# MainBoardR4.net
KiCad netlist of a schematic drawn in EAGLE
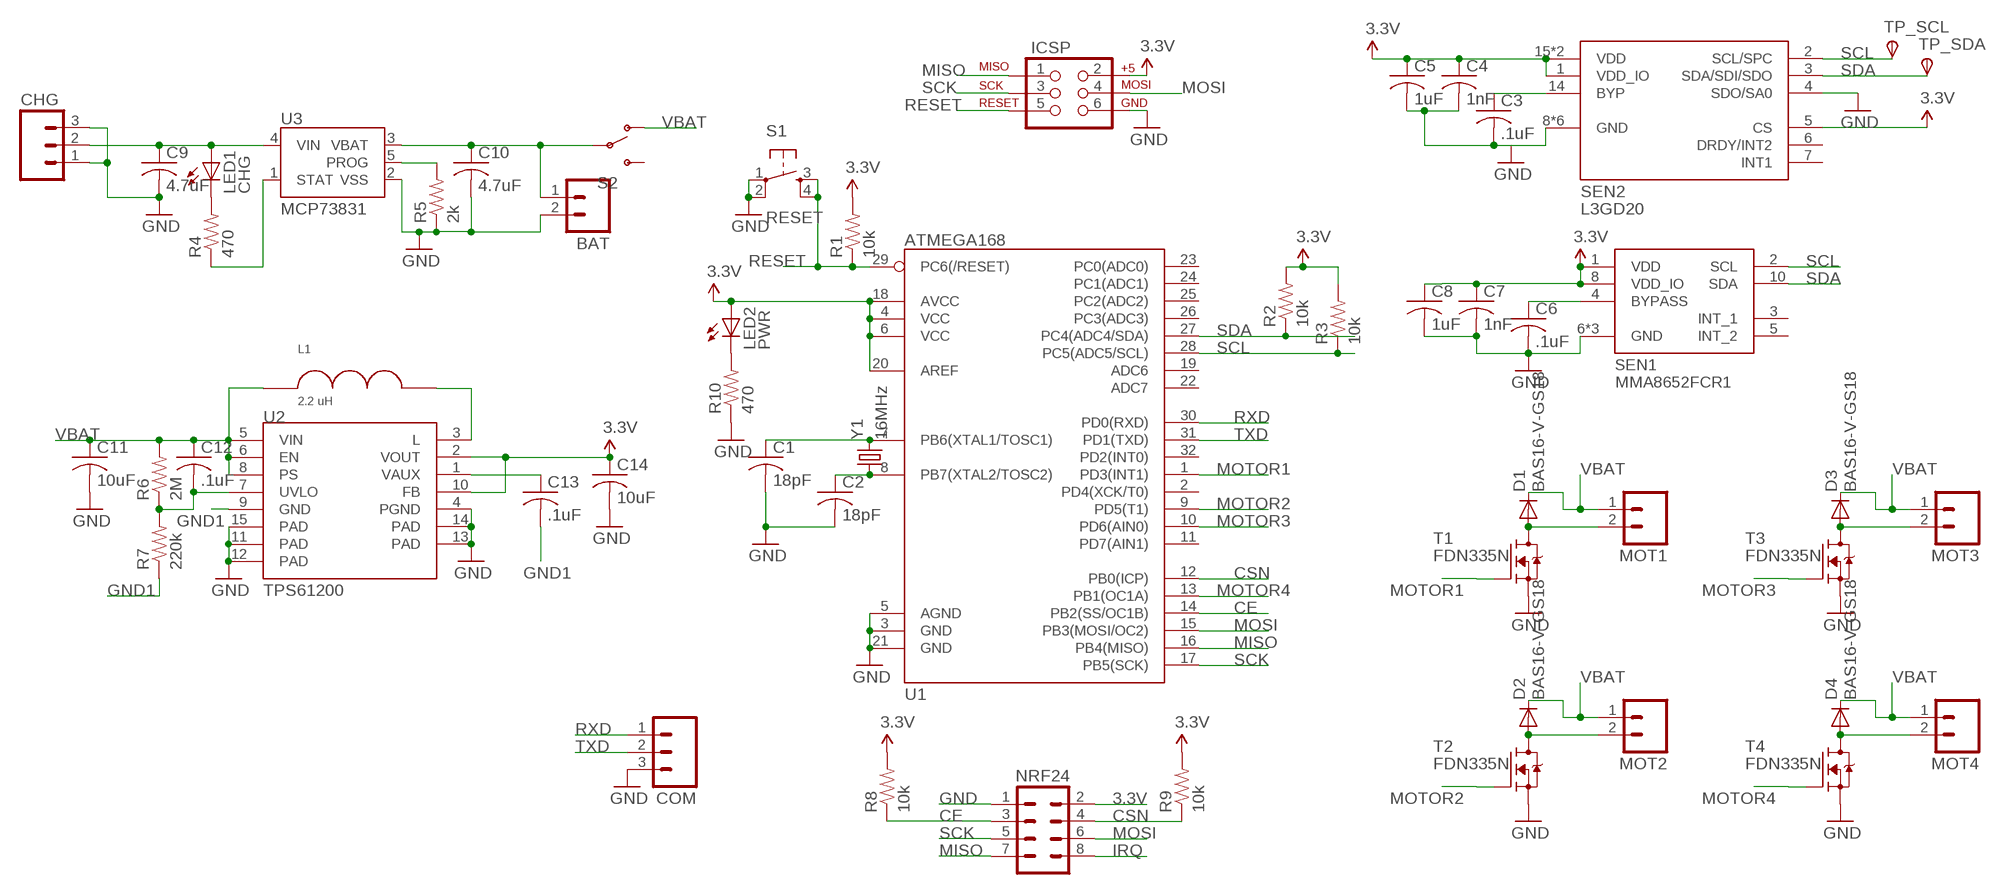
[diagram p0: schematic, sheet 1]

(export (version "E")
  (design (tool "Eeschema 10.0.6"))
  (components
    (comp (ref "BAT")
      (value "M02LOCK_LONGPADS")
      (footprint "eagle-import:1X02_LOCK_LONGPADS")
      (libsource (lib "eagle-import") (part "M02LOCK_LONGPADS"))
    )
    (comp (ref "C1")
      (value "18pF")
      (footprint "eagle-import:C0805")
      (libsource (lib "eagle-import") (part "C-USC0805"))
    )
    (comp (ref "C2")
      (value "18pF")
      (footprint "eagle-import:C0805")
      (libsource (lib "eagle-import") (part "C-USC0805"))
    )
    (comp (ref "C3")
      (value ".1uF")
      (footprint "eagle-import:C0805")
      (libsource (lib "eagle-import") (part "C-USC0805"))
    )
    (comp (ref "C4")
      (value "1nF")
      (footprint "eagle-import:C0805")
      (libsource (lib "eagle-import") (part "C-USC0805"))
    )
    (comp (ref "C5")
      (value "1uF")
      (footprint "eagle-import:C0805")
      (libsource (lib "eagle-import") (part "C-USC0805"))
    )
    (comp (ref "C6")
      (value ".1uF")
      (footprint "eagle-import:C0805")
      (libsource (lib "eagle-import") (part "C-USC0805"))
    )
    (comp (ref "C7")
      (value "1nF")
      (footprint "eagle-import:C0805")
      (libsource (lib "eagle-import") (part "C-USC0805"))
    )
    (comp (ref "C8")
      (value "1uF")
      (footprint "eagle-import:C0805")
      (libsource (lib "eagle-import") (part "C-USC0805"))
    )
    (comp (ref "C9")
      (value "4.7uF")
      (footprint "eagle-import:C0805")
      (libsource (lib "eagle-import") (part "C-USC0805"))
    )
    (comp (ref "C10")
      (value "4.7uF")
      (footprint "eagle-import:C0805")
      (libsource (lib "eagle-import") (part "C-USC0805"))
    )
    (comp (ref "C11")
      (value "10uF")
      (footprint "eagle-import:C0805")
      (libsource (lib "eagle-import") (part "C-USC0805"))
    )
    (comp (ref "C12")
      (value ".1uF")
      (footprint "eagle-import:C0805")
      (libsource (lib "eagle-import") (part "C-USC0805"))
    )
    (comp (ref "C13")
      (value ".1uF")
      (footprint "eagle-import:C0805")
      (libsource (lib "eagle-import") (part "C-USC0805"))
    )
    (comp (ref "C14")
      (value "10uF")
      (footprint "eagle-import:C0805")
      (libsource (lib "eagle-import") (part "C-USC0805"))
    )
    (comp (ref "CHG")
      (value "M03LONGPADS")
      (footprint "eagle-import:1X03_LONGPADS")
      (libsource (lib "eagle-import") (part "M03LONGPADS"))
    )
    (comp (ref "COM")
      (value "M03LONGPADS")
      (footprint "eagle-import:1X03_LONGPADS")
      (libsource (lib "eagle-import") (part "M03LONGPADS"))
    )
    (comp (ref "D1")
      (value "BAS16-V-GS18")
      (footprint "eagle-import:SOT23")
      (libsource (lib "eagle-import") (part "BAS16-V-GS18"))
    )
    (comp (ref "D2")
      (value "BAS16-V-GS18")
      (footprint "eagle-import:SOT23")
      (libsource (lib "eagle-import") (part "BAS16-V-GS18"))
    )
    (comp (ref "D3")
      (value "BAS16-V-GS18")
      (footprint "eagle-import:SOT23")
      (libsource (lib "eagle-import") (part "BAS16-V-GS18"))
    )
    (comp (ref "D4")
      (value "BAS16-V-GS18")
      (footprint "eagle-import:SOT23")
      (libsource (lib "eagle-import") (part "BAS16-V-GS18"))
    )
    (comp (ref "ICSP")
      (value "AVR_SPI_PRG_62X3_LOCK")
      (footprint "eagle-import:2X3_LOCK")
      (libsource (lib "eagle-import") (part "AVR_SPI_PRG_62X3_LOCK"))
    )
    (comp (ref "L1")
      (value "2.2 uH")
      (footprint "eagle-import:2518")
      (libsource (lib "eagle-import") (part "BRHL2518T2R2M"))
    )
    (comp (ref "LED1")
      (value "CHG")
      (footprint "eagle-import:LED-1206")
      (libsource (lib "eagle-import") (part "LED1206"))
    )
    (comp (ref "LED2")
      (value "PWR")
      (footprint "eagle-import:LED-1206")
      (libsource (lib "eagle-import") (part "LED1206"))
    )
    (comp (ref "MOT1")
      (value "M02LOCK_LONGPADS")
      (footprint "eagle-import:1X02_LOCK_LONGPADS")
      (libsource (lib "eagle-import") (part "M02LOCK_LONGPADS"))
    )
    (comp (ref "MOT2")
      (value "M02LOCK_LONGPADS")
      (footprint "eagle-import:1X02_LOCK_LONGPADS")
      (libsource (lib "eagle-import") (part "M02LOCK_LONGPADS"))
    )
    (comp (ref "MOT3")
      (value "M02LOCK_LONGPADS")
      (footprint "eagle-import:1X02_LOCK_LONGPADS")
      (libsource (lib "eagle-import") (part "M02LOCK_LONGPADS"))
    )
    (comp (ref "MOT4")
      (value "M02LOCK_LONGPADS")
      (footprint "eagle-import:1X02_LOCK_LONGPADS")
      (libsource (lib "eagle-import") (part "M02LOCK_LONGPADS"))
    )
    (comp (ref "NRF24")
      (value "M04X2")
      (footprint "eagle-import:2X4")
      (libsource (lib "eagle-import") (part "M04X2"))
    )
    (comp (ref "R1")
      (value "10k")
      (footprint "eagle-import:0805")
      (libsource (lib "eagle-import") (part "RESISTOR0805-RES"))
    )
    (comp (ref "R2")
      (value "10k")
      (footprint "eagle-import:0805")
      (libsource (lib "eagle-import") (part "RESISTOR0805-RES"))
    )
    (comp (ref "R3")
      (value "10k")
      (footprint "eagle-import:0805")
      (libsource (lib "eagle-import") (part "RESISTOR0805-RES"))
    )
    (comp (ref "R4")
      (value "470")
      (footprint "eagle-import:0805")
      (libsource (lib "eagle-import") (part "RESISTOR0805-RES"))
    )
    (comp (ref "R5")
      (value "2k")
      (footprint "eagle-import:0805")
      (libsource (lib "eagle-import") (part "RESISTOR0805-RES"))
    )
    (comp (ref "R6")
      (value "2M")
      (footprint "eagle-import:0805")
      (libsource (lib "eagle-import") (part "RESISTOR0805-RES"))
    )
    (comp (ref "R7")
      (value "220k")
      (footprint "eagle-import:0805")
      (libsource (lib "eagle-import") (part "RESISTOR0805-RES"))
    )
    (comp (ref "R8")
      (value "10k")
      (footprint "eagle-import:0805")
      (libsource (lib "eagle-import") (part "RESISTOR0805-RES"))
    )
    (comp (ref "R9")
      (value "10k")
      (footprint "eagle-import:0805")
      (libsource (lib "eagle-import") (part "RESISTOR0805-RES"))
    )
    (comp (ref "R10")
      (value "470")
      (footprint "eagle-import:0805")
      (libsource (lib "eagle-import") (part "RESISTOR0805-RES"))
    )
    (comp (ref "S1")
      (value "RESET")
      (footprint "eagle-import:TACTILE_SWITCH_SMD")
      (libsource (lib "eagle-import") (part "TAC_SWITCHSMD"))
    )
    (comp (ref "S2")
      (value "SWITCH-SPST-SMD-A")
      (footprint "eagle-import:SWITCH-SPST-SMD-A")
      (libsource (lib "eagle-import") (part "SWITCH-SPST-SMD-A"))
    )
    (comp (ref "SEN1")
      (value "MMA8652FCR1")
      (footprint "eagle-import:10_PIN_DFN")
      (libsource (lib "eagle-import") (part "MMA8652FCR1"))
    )
    (comp (ref "SEN2")
      (value "L3GD20")
      (footprint "eagle-import:LGA-16")
      (libsource (lib "eagle-import") (part "L3GD20"))
    )
    (comp (ref "T1")
      (value "FDN335N")
      (footprint "eagle-import:SOT23")
      (libsource (lib "eagle-import") (part "FDN335N"))
    )
    (comp (ref "T2")
      (value "FDN335N")
      (footprint "eagle-import:SOT23")
      (libsource (lib "eagle-import") (part "FDN335N"))
    )
    (comp (ref "T3")
      (value "FDN335N")
      (footprint "eagle-import:SOT23")
      (libsource (lib "eagle-import") (part "FDN335N"))
    )
    (comp (ref "T4")
      (value "FDN335N")
      (footprint "eagle-import:SOT23")
      (libsource (lib "eagle-import") (part "FDN335N"))
    )
    (comp (ref "TP_SCL")
      (value "TPSTP14SQ")
      (footprint "eagle-import:TP14SQ")
      (libsource (lib "eagle-import") (part "TPSTP14SQ"))
    )
    (comp (ref "TP_SDA")
      (value "TPSTP14SQ")
      (footprint "eagle-import:TP14SQ")
      (libsource (lib "eagle-import") (part "TPSTP14SQ"))
    )
    (comp (ref "U1")
      (value "ATMEGA168")
      (footprint "eagle-import:TQFP32-08")
      (libsource (lib "eagle-import") (part "ATMEGA168"))
    )
    (comp (ref "U2")
      (value "TPS61200")
      (footprint "eagle-import:QFN-10_PAD")
      (libsource (lib "eagle-import") (part "TPS61200"))
    )
    (comp (ref "U3")
      (value "MCP73831")
      (footprint "eagle-import:SOT23-5")
      (libsource (lib "eagle-import") (part "MCP73831"))
    )
    (comp (ref "Y1")
      (value "16MHz")
      (footprint "eagle-import:CRYSTAL-SMD-10.5X4.8-2PIN")
      (libsource (lib "eagle-import") (part "CRYSTAL10.5X4.8"))
    )
  )
  (nets
    (net (code "1") (name "/CE") (class "Default")
      (node (ref "NRF24") (pin "3") (pinfunction "3_3") (pintype "passive"))
      (node (ref "R8") (pin "1") (pinfunction "1_1") (pintype "passive"))
      (node (ref "U1") (pin "14") (pinfunction "PB2(SS/OC1B)_14") (pintype "bidirectional"))
    )
    (net (code "2") (name "/CSN") (class "Default")
      (node (ref "NRF24") (pin "4") (pinfunction "4_4") (pintype "passive"))
      (node (ref "R9") (pin "1") (pinfunction "1_1") (pintype "passive"))
      (node (ref "U1") (pin "12") (pinfunction "PB0(ICP)_12") (pintype "bidirectional"))
    )
    (net (code "3") (name "/GND1") (class "Default")
      (node (ref "C13") (pin "2") (pinfunction "2_2") (pintype "passive"))
      (node (ref "R7") (pin "1") (pinfunction "1_1") (pintype "passive"))
      (node (ref "U2") (pin "9") (pinfunction "GND_9") (pintype "power_in"))
    )
    (net (code "4") (name "/IRQ") (class "Default")
      (node (ref "NRF24") (pin "8") (pinfunction "8_8") (pintype "passive"))
    )
    (net (code "5") (name "/MISO") (class "Default")
      (node (ref "ICSP") (pin "1") (pinfunction "1_1") (pintype "passive"))
      (node (ref "NRF24") (pin "7") (pinfunction "7_7") (pintype "passive"))
      (node (ref "U1") (pin "16") (pinfunction "PB4(MISO)_16") (pintype "bidirectional"))
    )
    (net (code "6") (name "/MOSI") (class "Default")
      (node (ref "ICSP") (pin "4") (pinfunction "4_4") (pintype "passive"))
      (node (ref "NRF24") (pin "6") (pinfunction "6_6") (pintype "passive"))
      (node (ref "U1") (pin "15") (pinfunction "PB3(MOSI/OC2)_15") (pintype "bidirectional"))
    )
    (net (code "7") (name "/MOTOR1") (class "Default")
      (node (ref "T1") (pin "1") (pinfunction "G_1") (pintype "passive"))
      (node (ref "U1") (pin "1") (pinfunction "PD3(INT1)_1") (pintype "bidirectional"))
    )
    (net (code "8") (name "/MOTOR2") (class "Default")
      (node (ref "T2") (pin "1") (pinfunction "G_1") (pintype "passive"))
      (node (ref "U1") (pin "9") (pinfunction "PD5(T1)_9") (pintype "bidirectional"))
    )
    (net (code "9") (name "/MOTOR3") (class "Default")
      (node (ref "T3") (pin "1") (pinfunction "G_1") (pintype "passive"))
      (node (ref "U1") (pin "10") (pinfunction "PD6(AIN0)_10") (pintype "bidirectional"))
    )
    (net (code "10") (name "/MOTOR4") (class "Default")
      (node (ref "T4") (pin "1") (pinfunction "G_1") (pintype "passive"))
      (node (ref "U1") (pin "13") (pinfunction "PB1(OC1A)_13") (pintype "bidirectional"))
    )
    (net (code "11") (name "/RESET") (class "Default")
      (node (ref "ICSP") (pin "5") (pinfunction "5_5") (pintype "passive"))
      (node (ref "R1") (pin "1") (pinfunction "1_1") (pintype "passive"))
      (node (ref "S1") (pin "3") (pinfunction "3_3") (pintype "passive"))
      (node (ref "S1") (pin "4") (pinfunction "4_4") (pintype "passive"))
      (node (ref "U1") (pin "29") (pinfunction "PC6(/RESET)_29") (pintype "bidirectional"))
    )
    (net (code "12") (name "/RXD") (class "Default")
      (node (ref "COM") (pin "1") (pinfunction "1_1") (pintype "passive"))
      (node (ref "U1") (pin "30") (pinfunction "PD0(RXD)_30") (pintype "bidirectional"))
    )
    (net (code "13") (name "/SCK") (class "Default")
      (node (ref "ICSP") (pin "3") (pinfunction "3_3") (pintype "passive"))
      (node (ref "NRF24") (pin "5") (pinfunction "5_5") (pintype "passive"))
      (node (ref "U1") (pin "17") (pinfunction "PB5(SCK)_17") (pintype "bidirectional"))
    )
    (net (code "14") (name "/SCL") (class "Default")
      (node (ref "R3") (pin "1") (pinfunction "1_1") (pintype "passive"))
      (node (ref "SEN1") (pin "2") (pinfunction "SCL_2") (pintype "bidirectional"))
      (node (ref "SEN2") (pin "2") (pinfunction "SCL/SPC_2") (pintype "bidirectional"))
      (node (ref "TP_SCL") (pin "TP") (pinfunction "PP_TP") (pintype "input"))
      (node (ref "U1") (pin "28") (pinfunction "PC5(ADC5/SCL)_28") (pintype "bidirectional"))
    )
    (net (code "15") (name "/SDA") (class "Default")
      (node (ref "R2") (pin "1") (pinfunction "1_1") (pintype "passive"))
      (node (ref "SEN1") (pin "10") (pinfunction "SDA_10") (pintype "bidirectional"))
      (node (ref "SEN2") (pin "3") (pinfunction "SDA/SDI/SDO_3") (pintype "bidirectional"))
      (node (ref "TP_SDA") (pin "TP") (pinfunction "PP_TP") (pintype "input"))
      (node (ref "U1") (pin "27") (pinfunction "PC4(ADC4/SDA)_27") (pintype "bidirectional"))
    )
    (net (code "16") (name "/TXD") (class "Default")
      (node (ref "COM") (pin "2") (pinfunction "2_2") (pintype "passive"))
      (node (ref "U1") (pin "31") (pinfunction "PD1(TXD)_31") (pintype "bidirectional"))
    )
    (net (code "17") (name "/VBAT") (class "Default")
      (node (ref "C11") (pin "1") (pinfunction "1_1") (pintype "passive"))
      (node (ref "C12") (pin "1") (pinfunction "1_1") (pintype "passive"))
      (node (ref "D1") (pin "3") (pinfunction "C_3") (pintype "passive"))
      (node (ref "D2") (pin "3") (pinfunction "C_3") (pintype "passive"))
      (node (ref "D3") (pin "3") (pinfunction "C_3") (pintype "passive"))
      (node (ref "D4") (pin "3") (pinfunction "C_3") (pintype "passive"))
      (node (ref "L1") (pin "P$1") (pinfunction "1_P$1") (pintype "bidirectional"))
      (node (ref "MOT1") (pin "1") (pinfunction "1_1") (pintype "passive"))
      (node (ref "MOT2") (pin "1") (pinfunction "1_1") (pintype "passive"))
      (node (ref "MOT3") (pin "1") (pinfunction "1_1") (pintype "passive"))
      (node (ref "MOT4") (pin "1") (pinfunction "1_1") (pintype "passive"))
      (node (ref "R6") (pin "2") (pinfunction "2_2") (pintype "passive"))
      (node (ref "S2") (pin "1") (pinfunction "O_1") (pintype "passive"))
      (node (ref "U2") (pin "5") (pinfunction "VIN_5") (pintype "power_in"))
      (node (ref "U2") (pin "6") (pinfunction "EN_6") (pintype "input"))
      (node (ref "U2") (pin "8") (pinfunction "PS_8") (pintype "input"))
    )
    (net (code "18") (name "3.3V") (class "Default")
      (node (ref "C14") (pin "1") (pinfunction "1_1") (pintype "passive"))
      (node (ref "C4") (pin "1") (pinfunction "1_1") (pintype "passive"))
      (node (ref "C5") (pin "1") (pinfunction "1_1") (pintype "passive"))
      (node (ref "C7") (pin "1") (pinfunction "1_1") (pintype "passive"))
      (node (ref "C8") (pin "1") (pinfunction "1_1") (pintype "passive"))
      (node (ref "ICSP") (pin "2") (pinfunction "2_2") (pintype "passive"))
      (node (ref "LED2") (pin "A") (pinfunction "A_A") (pintype "passive"))
      (node (ref "NRF24") (pin "2") (pinfunction "2_2") (pintype "passive"))
      (node (ref "R1") (pin "2") (pinfunction "2_2") (pintype "passive"))
      (node (ref "R2") (pin "2") (pinfunction "2_2") (pintype "passive"))
      (node (ref "R3") (pin "2") (pinfunction "2_2") (pintype "passive"))
      (node (ref "R8") (pin "2") (pinfunction "2_2") (pintype "passive"))
      (node (ref "R9") (pin "2") (pinfunction "2_2") (pintype "passive"))
      (node (ref "SEN1") (pin "1") (pinfunction "VDD_1") (pintype "bidirectional"))
      (node (ref "SEN1") (pin "8") (pinfunction "VDD_IO_8") (pintype "bidirectional"))
      (node (ref "SEN2") (pin "1") (pinfunction "VDD_IO_1") (pintype "bidirectional"))
      (node (ref "SEN2") (pin "15") (pinfunction "VDD_15") (pintype "bidirectional"))
      (node (ref "SEN2") (pin "16") (pinfunction "VDD_16") (pintype "bidirectional"))
      (node (ref "SEN2") (pin "5") (pinfunction "CS_5") (pintype "bidirectional"))
      (node (ref "U1") (pin "18") (pinfunction "AVCC_18") (pintype "bidirectional"))
      (node (ref "U1") (pin "20") (pinfunction "AREF_20") (pintype "bidirectional"))
      (node (ref "U1") (pin "4") (pinfunction "VCC_4") (pintype "bidirectional"))
      (node (ref "U1") (pin "6") (pinfunction "VCC_6") (pintype "bidirectional"))
      (node (ref "U2") (pin "10") (pinfunction "FB_10") (pintype "passive"))
      (node (ref "U2") (pin "2") (pinfunction "VOUT_2") (pintype "passive"))
    )
    (net (code "19") (name "GND") (class "Default")
      (node (ref "BAT") (pin "2") (pinfunction "2_2") (pintype "passive"))
      (node (ref "C1") (pin "2") (pinfunction "2_2") (pintype "passive"))
      (node (ref "C10") (pin "2") (pinfunction "2_2") (pintype "passive"))
      (node (ref "C11") (pin "2") (pinfunction "2_2") (pintype "passive"))
      (node (ref "C14") (pin "2") (pinfunction "2_2") (pintype "passive"))
      (node (ref "C2") (pin "2") (pinfunction "2_2") (pintype "passive"))
      (node (ref "C3") (pin "2") (pinfunction "2_2") (pintype "passive"))
      (node (ref "C4") (pin "2") (pinfunction "2_2") (pintype "passive"))
      (node (ref "C5") (pin "2") (pinfunction "2_2") (pintype "passive"))
      (node (ref "C6") (pin "2") (pinfunction "2_2") (pintype "passive"))
      (node (ref "C7") (pin "2") (pinfunction "2_2") (pintype "passive"))
      (node (ref "C8") (pin "2") (pinfunction "2_2") (pintype "passive"))
      (node (ref "C9") (pin "2") (pinfunction "2_2") (pintype "passive"))
      (node (ref "CHG") (pin "1") (pinfunction "1_1") (pintype "passive"))
      (node (ref "CHG") (pin "3") (pinfunction "3_3") (pintype "passive"))
      (node (ref "COM") (pin "3") (pinfunction "3_3") (pintype "passive"))
      (node (ref "ICSP") (pin "6") (pinfunction "6_6") (pintype "passive"))
      (node (ref "NRF24") (pin "1") (pinfunction "1_1") (pintype "passive"))
      (node (ref "R10") (pin "1") (pinfunction "1_1") (pintype "passive"))
      (node (ref "R5") (pin "1") (pinfunction "1_1") (pintype "passive"))
      (node (ref "S1") (pin "1") (pinfunction "1_1") (pintype "passive"))
      (node (ref "S1") (pin "2") (pinfunction "2_2") (pintype "passive"))
      (node (ref "SEN1") (pin "6") (pinfunction "GND_6") (pintype "bidirectional"))
      (node (ref "SEN1") (pin "7") (pinfunction "GND_7") (pintype "bidirectional"))
      (node (ref "SEN1") (pin "9") (pinfunction "GND_9") (pintype "bidirectional"))
      (node (ref "SEN2") (pin "10") (pinfunction "GND_10") (pintype "bidirectional"))
      (node (ref "SEN2") (pin "11") (pinfunction "GND_11") (pintype "bidirectional"))
      (node (ref "SEN2") (pin "12") (pinfunction "GND_12") (pintype "bidirectional"))
      (node (ref "SEN2") (pin "13") (pinfunction "GND_13") (pintype "bidirectional"))
      (node (ref "SEN2") (pin "4") (pinfunction "SDO/SA0_4") (pintype "bidirectional"))
      (node (ref "SEN2") (pin "8") (pinfunction "GND_8") (pintype "bidirectional"))
      (node (ref "SEN2") (pin "9") (pinfunction "GND_9") (pintype "bidirectional"))
      (node (ref "T1") (pin "2") (pinfunction "S_2") (pintype "passive"))
      (node (ref "T2") (pin "2") (pinfunction "S_2") (pintype "passive"))
      (node (ref "T3") (pin "2") (pinfunction "S_2") (pintype "passive"))
      (node (ref "T4") (pin "2") (pinfunction "S_2") (pintype "passive"))
      (node (ref "U1") (pin "21") (pinfunction "GND_21") (pintype "bidirectional"))
      (node (ref "U1") (pin "3") (pinfunction "GND_3") (pintype "bidirectional"))
      (node (ref "U1") (pin "5") (pinfunction "AGND_5") (pintype "bidirectional"))
      (node (ref "U2") (pin "11") (pinfunction "PAD_11") (pintype "power_in"))
      (node (ref "U2") (pin "12") (pinfunction "PAD_12") (pintype "power_in"))
      (node (ref "U2") (pin "13") (pinfunction "PAD_13") (pintype "power_in"))
      (node (ref "U2") (pin "14") (pinfunction "PAD_14") (pintype "power_in"))
      (node (ref "U2") (pin "15") (pinfunction "PAD_15") (pintype "power_in"))
      (node (ref "U2") (pin "4") (pinfunction "PGND_4") (pintype "power_in"))
      (node (ref "U3") (pin "2") (pinfunction "VSS_2") (pintype "power_in"))
    )
    (net (code "20") (name "Net-(D1-A)") (class "Default")
      (node (ref "D1") (pin "1") (pinfunction "A_1") (pintype "passive"))
      (node (ref "MOT1") (pin "2") (pinfunction "2_2") (pintype "passive"))
      (node (ref "T1") (pin "3") (pinfunction "D_3") (pintype "passive"))
    )
    (net (code "21") (name "Net-(D2-A)") (class "Default")
      (node (ref "D2") (pin "1") (pinfunction "A_1") (pintype "passive"))
      (node (ref "MOT2") (pin "2") (pinfunction "2_2") (pintype "passive"))
      (node (ref "T2") (pin "3") (pinfunction "D_3") (pintype "passive"))
    )
    (net (code "22") (name "Net-(D3-A)") (class "Default")
      (node (ref "D3") (pin "1") (pinfunction "A_1") (pintype "passive"))
      (node (ref "MOT3") (pin "2") (pinfunction "2_2") (pintype "passive"))
      (node (ref "T3") (pin "3") (pinfunction "D_3") (pintype "passive"))
    )
    (net (code "23") (name "Net-(D4-A)") (class "Default")
      (node (ref "D4") (pin "1") (pinfunction "A_1") (pintype "passive"))
      (node (ref "MOT4") (pin "2") (pinfunction "2_2") (pintype "passive"))
      (node (ref "T4") (pin "3") (pinfunction "D_3") (pintype "passive"))
    )
    (net (code "24") (name "Net-(L1-2)") (class "Default")
      (node (ref "L1") (pin "P$2") (pinfunction "2_P$2") (pintype "bidirectional"))
      (node (ref "U2") (pin "3") (pinfunction "L_3") (pintype "passive"))
    )
    (net (code "25") (name "Net-(LED1-PadC)") (class "Default")
      (node (ref "LED1") (pin "C") (pinfunction "C_C") (pintype "passive"))
      (node (ref "R4") (pin "2") (pinfunction "2_2") (pintype "passive"))
    )
    (net (code "26") (name "Net-(LED2-PadC)") (class "Default")
      (node (ref "LED2") (pin "C") (pinfunction "C_C") (pintype "passive"))
      (node (ref "R10") (pin "2") (pinfunction "2_2") (pintype "passive"))
    )
    (net (code "27") (name "Net-(S2-P)") (class "Default")
      (node (ref "BAT") (pin "1") (pinfunction "1_1") (pintype "passive"))
      (node (ref "C10") (pin "1") (pinfunction "1_1") (pintype "passive"))
      (node (ref "S2") (pin "2") (pinfunction "P_2") (pintype "passive"))
      (node (ref "U3") (pin "3") (pinfunction "VBAT_3") (pintype "power_in"))
    )
    (net (code "28") (name "Net-(SEN1-BYPASS)") (class "Default")
      (node (ref "C6") (pin "1") (pinfunction "1_1") (pintype "passive"))
      (node (ref "SEN1") (pin "4") (pinfunction "BYPASS_4") (pintype "bidirectional"))
    )
    (net (code "29") (name "Net-(SEN2-BYP)") (class "Default")
      (node (ref "C3") (pin "1") (pinfunction "1_1") (pintype "passive"))
      (node (ref "SEN2") (pin "14") (pinfunction "BYP_14") (pintype "bidirectional"))
    )
    (net (code "30") (name "Net-(U1-PB6(XTAL1{slash}TOSC1))") (class "Default")
      (node (ref "C1") (pin "1") (pinfunction "1_1") (pintype "passive"))
      (node (ref "U1") (pin "7") (pinfunction "PB6(XTAL1/TOSC1)_7") (pintype "bidirectional"))
      (node (ref "Y1") (pin "P$2") (pinfunction "2_P$2") (pintype "passive"))
    )
    (net (code "31") (name "Net-(U1-PB7(XTAL2{slash}TOSC2))") (class "Default")
      (node (ref "C2") (pin "1") (pinfunction "1_1") (pintype "passive"))
      (node (ref "U1") (pin "8") (pinfunction "PB7(XTAL2/TOSC2)_8") (pintype "bidirectional"))
      (node (ref "Y1") (pin "P$1") (pinfunction "1_P$1") (pintype "passive"))
    )
    (net (code "32") (name "Net-(U2-UVLO)") (class "Default")
      (node (ref "C12") (pin "2") (pinfunction "2_2") (pintype "passive"))
      (node (ref "R6") (pin "1") (pinfunction "1_1") (pintype "passive"))
      (node (ref "R7") (pin "2") (pinfunction "2_2") (pintype "passive"))
      (node (ref "U2") (pin "7") (pinfunction "UVLO_7") (pintype "passive"))
    )
    (net (code "33") (name "Net-(U2-VAUX)") (class "Default")
      (node (ref "C13") (pin "1") (pinfunction "1_1") (pintype "passive"))
      (node (ref "U2") (pin "1") (pinfunction "VAUX_1") (pintype "passive"))
    )
    (net (code "34") (name "Net-(U3-PROG)") (class "Default")
      (node (ref "R5") (pin "2") (pinfunction "2_2") (pintype "passive"))
      (node (ref "U3") (pin "5") (pinfunction "PROG_5") (pintype "input"))
    )
    (net (code "35") (name "Net-(U3-STAT)") (class "Default")
      (node (ref "R4") (pin "1") (pinfunction "1_1") (pintype "passive"))
      (node (ref "U3") (pin "1") (pinfunction "STAT_1") (pintype "output"))
    )
    (net (code "36") (name "Net-(U3-VIN)") (class "Default")
      (node (ref "C9") (pin "1") (pinfunction "1_1") (pintype "passive"))
      (node (ref "CHG") (pin "2") (pinfunction "2_2") (pintype "passive"))
      (node (ref "LED1") (pin "A") (pinfunction "A_A") (pintype "passive"))
      (node (ref "U3") (pin "4") (pinfunction "VIN_4") (pintype "power_in"))
    )
    (net (code "37") (name "unconnected-(S2-S-Pad3)") (class "Default")
      (node (ref "S2") (pin "3") (pinfunction "S_3") (pintype "passive"))
    )
    (net (code "38") (name "unconnected-(SEN1-INT_1-Pad3)") (class "Default")
      (node (ref "SEN1") (pin "3") (pinfunction "INT_1_3") (pintype "bidirectional"))
    )
    (net (code "39") (name "unconnected-(SEN1-INT_2-Pad5)") (class "Default")
      (node (ref "SEN1") (pin "5") (pinfunction "INT_2_5") (pintype "bidirectional"))
    )
    (net (code "40") (name "unconnected-(SEN2-DRDY{slash}INT2-Pad6)") (class "Default")
      (node (ref "SEN2") (pin "6") (pinfunction "DRDY/INT2_6") (pintype "bidirectional"))
    )
    (net (code "41") (name "unconnected-(SEN2-INT1-Pad7)") (class "Default")
      (node (ref "SEN2") (pin "7") (pinfunction "INT1_7") (pintype "bidirectional"))
    )
    (net (code "42") (name "unconnected-(U1-ADC6-Pad19)") (class "Default")
      (node (ref "U1") (pin "19") (pinfunction "ADC6_19") (pintype "bidirectional"))
    )
    (net (code "43") (name "unconnected-(U1-ADC7-Pad22)") (class "Default")
      (node (ref "U1") (pin "22") (pinfunction "ADC7_22") (pintype "bidirectional"))
    )
    (net (code "44") (name "unconnected-(U1-PC0(ADC0)-Pad23)") (class "Default")
      (node (ref "U1") (pin "23") (pinfunction "PC0(ADC0)_23") (pintype "bidirectional"))
    )
    (net (code "45") (name "unconnected-(U1-PC1(ADC1)-Pad24)") (class "Default")
      (node (ref "U1") (pin "24") (pinfunction "PC1(ADC1)_24") (pintype "bidirectional"))
    )
    (net (code "46") (name "unconnected-(U1-PC2(ADC2)-Pad25)") (class "Default")
      (node (ref "U1") (pin "25") (pinfunction "PC2(ADC2)_25") (pintype "bidirectional"))
    )
    (net (code "47") (name "unconnected-(U1-PC3(ADC3)-Pad26)") (class "Default")
      (node (ref "U1") (pin "26") (pinfunction "PC3(ADC3)_26") (pintype "bidirectional"))
    )
    (net (code "48") (name "unconnected-(U1-PD2(INT0)-Pad32)") (class "Default")
      (node (ref "U1") (pin "32") (pinfunction "PD2(INT0)_32") (pintype "bidirectional"))
    )
    (net (code "49") (name "unconnected-(U1-PD4(XCK{slash}T0)-Pad2)") (class "Default")
      (node (ref "U1") (pin "2") (pinfunction "PD4(XCK/T0)_2") (pintype "bidirectional"))
    )
    (net (code "50") (name "unconnected-(U1-PD7(AIN1)-Pad11)") (class "Default")
      (node (ref "U1") (pin "11") (pinfunction "PD7(AIN1)_11") (pintype "bidirectional"))
    )
  )
)
